# twip-sb2.net
KiCad netlist of a schematic drawn in EAGLE
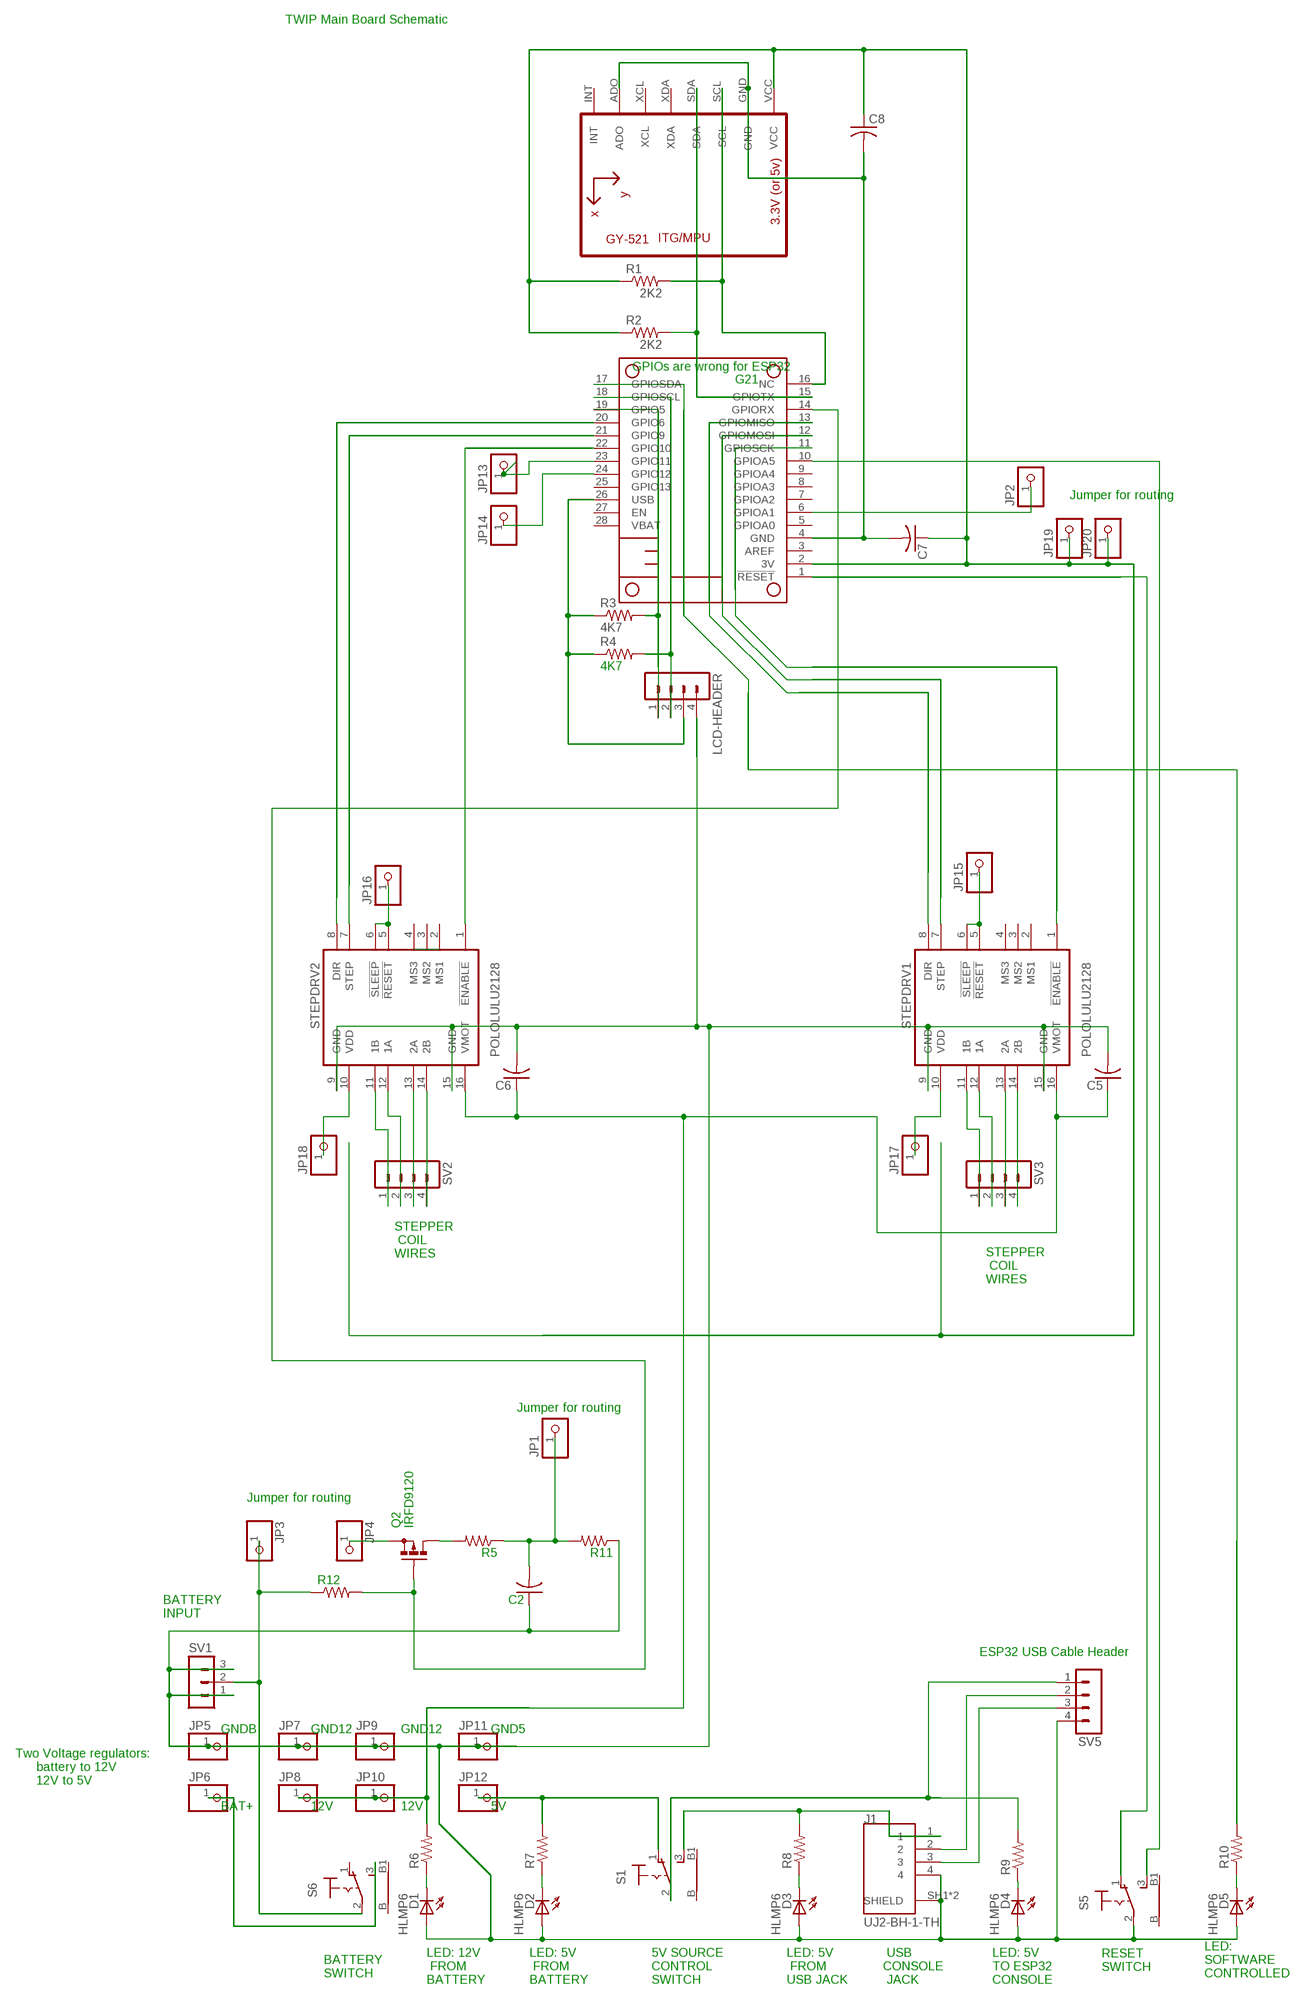
[diagram p0: schematic, sheet 1]

(export (version "E")
  (design (tool "Eeschema 10.0.6"))
  (components
    (comp (ref "C2")
      (value "C-US050-025X075")
      (footprint "eagle-import:C050-025X075")
      (libsource (lib "eagle-import") (part "C-US050-025X075"))
    )
    (comp (ref "C5")
      (value "C-US050-024X044")
      (footprint "eagle-import:C050-024X044")
      (libsource (lib "eagle-import") (part "C-US050-024X044"))
    )
    (comp (ref "C6")
      (value "C-US050-024X044")
      (footprint "eagle-import:C050-024X044")
      (libsource (lib "eagle-import") (part "C-US050-024X044"))
    )
    (comp (ref "C7")
      (value "C-US050-024X044")
      (footprint "eagle-import:C050-024X044")
      (libsource (lib "eagle-import") (part "C-US050-024X044"))
    )
    (comp (ref "C8")
      (value "C-US050-024X044")
      (footprint "eagle-import:C050-024X044")
      (libsource (lib "eagle-import") (part "C-US050-024X044"))
    )
    (comp (ref "D1")
      (value "HLMP6")
      (footprint "eagle-import:HLMP6")
      (fields (field (name "MF") "AGILENT TECHNOLOGIES") (field (name "MPN") "HLMP-6500"))
      (libsource (lib "eagle-import") (part "HLMP6"))
    )
    (comp (ref "D2")
      (value "HLMP6")
      (footprint "eagle-import:HLMP6")
      (fields (field (name "MF") "AGILENT TECHNOLOGIES") (field (name "MPN") "HLMP-6500"))
      (libsource (lib "eagle-import") (part "HLMP6"))
    )
    (comp (ref "D3")
      (value "HLMP6")
      (footprint "eagle-import:HLMP6")
      (fields (field (name "MF") "AGILENT TECHNOLOGIES") (field (name "MPN") "HLMP-6500"))
      (libsource (lib "eagle-import") (part "HLMP6"))
    )
    (comp (ref "D4")
      (value "HLMP6")
      (footprint "eagle-import:HLMP6")
      (fields (field (name "MF") "AGILENT TECHNOLOGIES") (field (name "MPN") "HLMP-6500"))
      (libsource (lib "eagle-import") (part "HLMP6"))
    )
    (comp (ref "D5")
      (value "HLMP6")
      (footprint "eagle-import:HLMP6")
      (fields (field (name "MF") "AGILENT TECHNOLOGIES") (field (name "MPN") "HLMP-6500"))
      (libsource (lib "eagle-import") (part "HLMP6"))
    )
    (comp (ref "J1")
      (value "UJ2-BH-1-TH")
      (footprint "eagle-import:CUI_UJ2-BH-1-TH")
      (fields (field (name "MANUFACTURER") "CUI INC"))
      (libsource (lib "eagle-import") (part "UJ2-BH-1-TH"))
    )
    (comp (ref "JP1")
      (value "PINHD-1X1")
      (footprint "eagle-import:1X01")
      (libsource (lib "eagle-import") (part "PINHD-1X1"))
    )
    (comp (ref "JP2")
      (value "PINHD-1X1")
      (footprint "eagle-import:1X01")
      (libsource (lib "eagle-import") (part "PINHD-1X1"))
    )
    (comp (ref "JP3")
      (value "PINHD-1X1")
      (footprint "eagle-import:1X01")
      (libsource (lib "eagle-import") (part "PINHD-1X1"))
    )
    (comp (ref "JP4")
      (value "PINHD-1X1")
      (footprint "eagle-import:1X01")
      (libsource (lib "eagle-import") (part "PINHD-1X1"))
    )
    (comp (ref "JP5")
      (value "PINHD-1X1")
      (footprint "eagle-import:1X01")
      (libsource (lib "eagle-import") (part "PINHD-1X1"))
    )
    (comp (ref "JP6")
      (value "PINHD-1X1")
      (footprint "eagle-import:1X01")
      (libsource (lib "eagle-import") (part "PINHD-1X1"))
    )
    (comp (ref "JP7")
      (value "PINHD-1X1")
      (footprint "eagle-import:1X01")
      (libsource (lib "eagle-import") (part "PINHD-1X1"))
    )
    (comp (ref "JP8")
      (value "PINHD-1X1")
      (footprint "eagle-import:1X01")
      (libsource (lib "eagle-import") (part "PINHD-1X1"))
    )
    (comp (ref "JP9")
      (value "PINHD-1X1")
      (footprint "eagle-import:1X01")
      (libsource (lib "eagle-import") (part "PINHD-1X1"))
    )
    (comp (ref "JP10")
      (value "PINHD-1X1")
      (footprint "eagle-import:1X01")
      (libsource (lib "eagle-import") (part "PINHD-1X1"))
    )
    (comp (ref "JP11")
      (value "PINHD-1X1")
      (footprint "eagle-import:1X01")
      (libsource (lib "eagle-import") (part "PINHD-1X1"))
    )
    (comp (ref "JP12")
      (value "PINHD-1X1")
      (footprint "eagle-import:1X01")
      (libsource (lib "eagle-import") (part "PINHD-1X1"))
    )
    (comp (ref "JP13")
      (value "PINHD-1X1")
      (footprint "eagle-import:1X01")
      (libsource (lib "eagle-import") (part "PINHD-1X1"))
    )
    (comp (ref "JP14")
      (value "PINHD-1X1")
      (footprint "eagle-import:1X01")
      (libsource (lib "eagle-import") (part "PINHD-1X1"))
    )
    (comp (ref "JP15")
      (value "PINHD-1X1")
      (footprint "eagle-import:1X01")
      (libsource (lib "eagle-import") (part "PINHD-1X1"))
    )
    (comp (ref "JP16")
      (value "PINHD-1X1")
      (footprint "eagle-import:1X01")
      (libsource (lib "eagle-import") (part "PINHD-1X1"))
    )
    (comp (ref "JP17")
      (value "PINHD-1X1")
      (footprint "eagle-import:1X01")
      (libsource (lib "eagle-import") (part "PINHD-1X1"))
    )
    (comp (ref "JP18")
      (value "PINHD-1X1")
      (footprint "eagle-import:1X01")
      (libsource (lib "eagle-import") (part "PINHD-1X1"))
    )
    (comp (ref "JP19")
      (value "PINHD-1X1")
      (footprint "eagle-import:1X01")
      (libsource (lib "eagle-import") (part "PINHD-1X1"))
    )
    (comp (ref "JP20")
      (value "PINHD-1X1")
      (footprint "eagle-import:1X01")
      (libsource (lib "eagle-import") (part "PINHD-1X1"))
    )
    (comp (ref "LCD-HEADER")
      (value "MA04-1")
      (footprint "eagle-import:MA04-1")
      (libsource (lib "eagle-import") (part "MA04-1"))
    )
    (comp (ref "MS2")
      (value "FEATHERWING_NOHOLES")
      (footprint "eagle-import:FEATHERWING_NOHOLES")
      (libsource (lib "eagle-import") (part "FEATHERWING_NOHOLES"))
    )
    (comp (ref "Q2")
      (value "IRFD9120")
      (footprint "eagle-import:C370-01")
      (libsource (lib "eagle-import") (part "IRFD9120"))
    )
    (comp (ref "R1")
      (value "2K2")
      (footprint "eagle-import:0309_12")
      (libsource (lib "eagle-import") (part "resistor_348_R-US_0309/12"))
    )
    (comp (ref "R2")
      (value "2K2")
      (footprint "eagle-import:0309_12")
      (libsource (lib "eagle-import") (part "resistor_348_R-US_0309/12"))
    )
    (comp (ref "R3")
      (value "4K7")
      (footprint "eagle-import:0309_12")
      (libsource (lib "eagle-import") (part "resistor_348_R-US_0309/12"))
    )
    (comp (ref "R4")
      (value "4K7")
      (footprint "eagle-import:0309_12")
      (libsource (lib "eagle-import") (part "resistor_348_R-US_0309/12"))
    )
    (comp (ref "R5")
      (value "R-US_0207/10")
      (footprint "eagle-import:0207_10")
      (libsource (lib "eagle-import") (part "R-US_0207/10"))
    )
    (comp (ref "R6")
      (value "R-US_0207/10")
      (footprint "eagle-import:0207_10")
      (libsource (lib "eagle-import") (part "R-US_0207/10"))
    )
    (comp (ref "R7")
      (value "R-US_0207/10")
      (footprint "eagle-import:0207_10")
      (libsource (lib "eagle-import") (part "R-US_0207/10"))
    )
    (comp (ref "R8")
      (value "R-US_0207/10")
      (footprint "eagle-import:0207_10")
      (libsource (lib "eagle-import") (part "R-US_0207/10"))
    )
    (comp (ref "R9")
      (value "R-US_0207/10")
      (footprint "eagle-import:0207_10")
      (libsource (lib "eagle-import") (part "R-US_0207/10"))
    )
    (comp (ref "R10")
      (value "R-US_0207/10")
      (footprint "eagle-import:0207_10")
      (libsource (lib "eagle-import") (part "R-US_0207/10"))
    )
    (comp (ref "R11")
      (value "R-US_0207/10")
      (footprint "eagle-import:0207_10")
      (libsource (lib "eagle-import") (part "R-US_0207/10"))
    )
    (comp (ref "R12")
      (value "R-US_0207/10")
      (footprint "eagle-import:0207_10")
      (libsource (lib "eagle-import") (part "R-US_0207/10"))
    )
    (comp (ref "S1")
      (value "9070-1W")
      (footprint "eagle-import:9070-1W")
      (libsource (lib "eagle-import") (part "9070-1W"))
    )
    (comp (ref "S5")
      (value "9070-1W")
      (footprint "eagle-import:9070-1W")
      (libsource (lib "eagle-import") (part "9070-1W"))
    )
    (comp (ref "S6")
      (value "9070-1W")
      (footprint "eagle-import:9070-1W")
      (libsource (lib "eagle-import") (part "9070-1W"))
    )
    (comp (ref "STEPDRV1")
      (value "POLOLULU2128")
      (footprint "eagle-import:POLOLULU2128")
      (libsource (lib "eagle-import") (part "POLOLULU2128"))
    )
    (comp (ref "STEPDRV2")
      (value "POLOLULU2128")
      (footprint "eagle-import:POLOLULU2128")
      (libsource (lib "eagle-import") (part "POLOLULU2128"))
    )
    (comp (ref "SV1")
      (value "MA03-1")
      (footprint "eagle-import:MA03-1")
      (libsource (lib "eagle-import") (part "MA03-1"))
    )
    (comp (ref "SV2")
      (value "MA04-1")
      (footprint "eagle-import:MA04-1")
      (libsource (lib "eagle-import") (part "MA04-1"))
    )
    (comp (ref "SV3")
      (value "MA04-1")
      (footprint "eagle-import:MA04-1")
      (libsource (lib "eagle-import") (part "MA04-1"))
    )
    (comp (ref "SV5")
      (value "MA04-1")
      (footprint "eagle-import:MA04-1")
      (libsource (lib "eagle-import") (part "MA04-1"))
    )
    (comp (ref "U1")
      (value "GY-521MPU6050")
      (footprint "eagle-import:GY-521")
      (libsource (lib "eagle-import") (part "GY-521MPU6050"))
    )
  )
  (nets
    (net (code "1") (name "/VBAT") (class "Default")
      (node (ref "MS2") (pin "28") (pinfunction "VBAT_28") (pintype "power_in"))
    )
    (net (code "2") (name "Net-(C2-Pad2)") (class "Default")
      (node (ref "C2") (pin "2") (pinfunction "2_2") (pintype "passive"))
      (node (ref "JP1") (pin "1") (pinfunction "1_1") (pintype "passive"))
      (node (ref "R11") (pin "2") (pinfunction "2_2") (pintype "passive"))
      (node (ref "R5") (pin "1") (pinfunction "1_1") (pintype "passive"))
    )
    (net (code "3") (name "Net-(D1-PadK)") (class "Default")
      (node (ref "D1") (pin "K") (pinfunction "K_K") (pintype "passive"))
      (node (ref "R6") (pin "1") (pinfunction "1_1") (pintype "passive"))
    )
    (net (code "4") (name "Net-(D2-PadK)") (class "Default")
      (node (ref "D2") (pin "K") (pinfunction "K_K") (pintype "passive"))
      (node (ref "R7") (pin "1") (pinfunction "1_1") (pintype "passive"))
    )
    (net (code "5") (name "Net-(D3-PadK)") (class "Default")
      (node (ref "D3") (pin "K") (pinfunction "K_K") (pintype "passive"))
      (node (ref "R8") (pin "1") (pinfunction "1_1") (pintype "passive"))
    )
    (net (code "6") (name "Net-(D4-PadK)") (class "Default")
      (node (ref "D4") (pin "K") (pinfunction "K_K") (pintype "passive"))
      (node (ref "R9") (pin "1") (pinfunction "1_1") (pintype "passive"))
    )
    (net (code "7") (name "Net-(D5-PadK)") (class "Default")
      (node (ref "D5") (pin "K") (pinfunction "K_K") (pintype "passive"))
      (node (ref "R10") (pin "1") (pinfunction "1_1") (pintype "passive"))
    )
    (net (code "8") (name "Net-(J1-Pad2)") (class "Default")
      (node (ref "J1") (pin "2") (pinfunction "2_2") (pintype "passive"))
      (node (ref "SV5") (pin "2") (pinfunction "2_2") (pintype "passive"))
    )
    (net (code "9") (name "Net-(J1-Pad3)") (class "Default")
      (node (ref "J1") (pin "3") (pinfunction "3_3") (pintype "passive"))
      (node (ref "SV5") (pin "3") (pinfunction "3_3") (pintype "passive"))
    )
    (net (code "10") (name "Net-(JP4-Pad1)") (class "Default")
      (node (ref "JP4") (pin "1") (pinfunction "1_1") (pintype "passive"))
      (node (ref "Q2") (pin "S") (pinfunction "S_S") (pintype "passive"))
    )
    (net (code "11") (name "Net-(MS2-3V)") (class "Default")
      (node (ref "C7") (pin "1") (pinfunction "1_1") (pintype "passive"))
      (node (ref "C8") (pin "1") (pinfunction "1_1") (pintype "passive"))
      (node (ref "JP19") (pin "1") (pinfunction "1_1") (pintype "passive"))
      (node (ref "JP20") (pin "1") (pinfunction "1_1") (pintype "passive"))
      (node (ref "MS2") (pin "2") (pinfunction "3V_2") (pintype "power_in"))
      (node (ref "R1") (pin "1") (pinfunction "1_1") (pintype "passive"))
      (node (ref "R2") (pin "1") (pinfunction "1_1") (pintype "passive"))
      (node (ref "U1") (pin "VCC") (pinfunction "VCC_VCC") (pintype "bidirectional"))
    )
    (net (code "12") (name "Net-(MS2-GND)") (class "Default")
      (node (ref "C7") (pin "2") (pinfunction "2_2") (pintype "passive"))
      (node (ref "C8") (pin "2") (pinfunction "2_2") (pintype "passive"))
      (node (ref "MS2") (pin "4") (pinfunction "GND_4") (pintype "power_in"))
      (node (ref "U1") (pin "ADO") (pinfunction "ADO_ADO") (pintype "bidirectional"))
      (node (ref "U1") (pin "GND") (pinfunction "GND_GND") (pintype "bidirectional"))
    )
    (net (code "13") (name "Net-(MS2-GPIO5)") (class "Default")
      (node (ref "LCD-HEADER") (pin "1") (pinfunction "1_1") (pintype "passive"))
      (node (ref "MS2") (pin "19") (pinfunction "GPIO5_19") (pintype "bidirectional"))
      (node (ref "R3") (pin "2") (pinfunction "2_2") (pintype "passive"))
    )
    (net (code "14") (name "Net-(MS2-GPIO6)") (class "Default")
      (node (ref "MS2") (pin "20") (pinfunction "GPIO6_20") (pintype "bidirectional"))
      (node (ref "STEPDRV2") (pin "8") (pinfunction "DIR_8") (pintype "input"))
    )
    (net (code "15") (name "Net-(MS2-GPIO9)") (class "Default")
      (node (ref "MS2") (pin "21") (pinfunction "GPIO9_21") (pintype "bidirectional"))
      (node (ref "STEPDRV2") (pin "7") (pinfunction "STEP_7") (pintype "input"))
    )
    (net (code "16") (name "Net-(MS2-GPIO10)") (class "Default")
      (node (ref "MS2") (pin "22") (pinfunction "GPIO10_22") (pintype "bidirectional"))
      (node (ref "STEPDRV2") (pin "1") (pinfunction "~{ENABLE}_1") (pintype "input"))
    )
    (net (code "17") (name "Net-(MS2-GPIO11)") (class "Default")
      (node (ref "JP13") (pin "1") (pinfunction "1_1") (pintype "passive"))
      (node (ref "MS2") (pin "23") (pinfunction "GPIO11_23") (pintype "bidirectional"))
    )
    (net (code "18") (name "Net-(MS2-GPIO12)") (class "Default")
      (node (ref "JP14") (pin "1") (pinfunction "1_1") (pintype "passive"))
      (node (ref "MS2") (pin "24") (pinfunction "GPIO12_24") (pintype "bidirectional"))
    )
    (net (code "19") (name "Net-(MS2-GPIOA1)") (class "Default")
      (node (ref "JP2") (pin "1") (pinfunction "1_1") (pintype "passive"))
      (node (ref "MS2") (pin "6") (pinfunction "GPIOA1_6") (pintype "bidirectional"))
    )
    (net (code "20") (name "Net-(MS2-GPIOA5)") (class "Default")
      (node (ref "MS2") (pin "10") (pinfunction "GPIOA5_10") (pintype "bidirectional"))
      (node (ref "S5") (pin "3") (pinfunction "S_3") (pintype "passive"))
    )
    (net (code "21") (name "Net-(MS2-GPIOMISO)") (class "Default")
      (node (ref "MS2") (pin "13") (pinfunction "GPIOMISO_13") (pintype "bidirectional"))
      (node (ref "STEPDRV1") (pin "8") (pinfunction "DIR_8") (pintype "input"))
    )
    (net (code "22") (name "Net-(MS2-GPIOMOSI)") (class "Default")
      (node (ref "MS2") (pin "12") (pinfunction "GPIOMOSI_12") (pintype "bidirectional"))
      (node (ref "STEPDRV1") (pin "7") (pinfunction "STEP_7") (pintype "input"))
    )
    (net (code "23") (name "Net-(MS2-GPIORX)") (class "Default")
      (node (ref "MS2") (pin "14") (pinfunction "GPIORX_14") (pintype "bidirectional"))
      (node (ref "Q2") (pin "G") (pinfunction "G_G") (pintype "passive"))
      (node (ref "R12") (pin "2") (pinfunction "2_2") (pintype "passive"))
    )
    (net (code "24") (name "Net-(MS2-GPIOSCK)") (class "Default")
      (node (ref "MS2") (pin "11") (pinfunction "GPIOSCK_11") (pintype "bidirectional"))
      (node (ref "STEPDRV1") (pin "1") (pinfunction "~{ENABLE}_1") (pintype "input"))
    )
    (net (code "25") (name "Net-(MS2-GPIOSCL)") (class "Default")
      (node (ref "LCD-HEADER") (pin "2") (pinfunction "2_2") (pintype "passive"))
      (node (ref "MS2") (pin "18") (pinfunction "GPIOSCL_18") (pintype "bidirectional"))
      (node (ref "R4") (pin "2") (pinfunction "2_2") (pintype "passive"))
    )
    (net (code "26") (name "Net-(MS2-GPIOSDA)") (class "Default")
      (node (ref "MS2") (pin "17") (pinfunction "GPIOSDA_17") (pintype "bidirectional"))
      (node (ref "R10") (pin "2") (pinfunction "2_2") (pintype "passive"))
    )
    (net (code "27") (name "Net-(MS2-GPIOTX)") (class "Default")
      (node (ref "MS2") (pin "15") (pinfunction "GPIOTX_15") (pintype "bidirectional"))
      (node (ref "R2") (pin "2") (pinfunction "2_2") (pintype "passive"))
      (node (ref "U1") (pin "SDA") (pinfunction "SDA_SDA") (pintype "bidirectional"))
    )
    (net (code "28") (name "Net-(MS2-NC)") (class "Default")
      (node (ref "MS2") (pin "16") (pinfunction "NC_16") (pintype "passive"))
      (node (ref "R1") (pin "2") (pinfunction "2_2") (pintype "passive"))
      (node (ref "U1") (pin "SCL") (pinfunction "SCL_SCL") (pintype "bidirectional"))
    )
    (net (code "29") (name "Net-(MS2-USB)") (class "Default")
      (node (ref "LCD-HEADER") (pin "3") (pinfunction "3_3") (pintype "passive"))
      (node (ref "MS2") (pin "26") (pinfunction "USB_26") (pintype "power_in"))
      (node (ref "R3") (pin "1") (pinfunction "1_1") (pintype "passive"))
      (node (ref "R4") (pin "1") (pinfunction "1_1") (pintype "passive"))
    )
    (net (code "30") (name "Net-(MS2-~{RESET})") (class "Default")
      (node (ref "MS2") (pin "1") (pinfunction "~{RESET}_1") (pintype "input"))
      (node (ref "S5") (pin "1") (pinfunction "O_1") (pintype "passive"))
    )
    (net (code "31") (name "Net-(Q2-D-PadD1)") (class "Default")
      (node (ref "Q2") (pin "D") (pinfunction "D_D") (pintype "passive"))
      (node (ref "Q2") (pin "D1") (pinfunction "D_D1") (pintype "passive"))
      (node (ref "R5") (pin "2") (pinfunction "2_2") (pintype "passive"))
    )
    (net (code "32") (name "Net-(S1-O)") (class "Default")
      (node (ref "JP12") (pin "1") (pinfunction "1_1") (pintype "passive"))
      (node (ref "R7") (pin "2") (pinfunction "2_2") (pintype "passive"))
      (node (ref "S1") (pin "1") (pinfunction "O_1") (pintype "passive"))
    )
    (net (code "33") (name "Net-(S1-P)") (class "Default")
      (node (ref "R9") (pin "2") (pinfunction "2_2") (pintype "passive"))
      (node (ref "S1") (pin "2") (pinfunction "P_2") (pintype "passive"))
      (node (ref "SV5") (pin "1") (pinfunction "1_1") (pintype "passive"))
    )
    (net (code "34") (name "Net-(S1-S)") (class "Default")
      (node (ref "J1") (pin "1") (pinfunction "1_1") (pintype "passive"))
      (node (ref "R8") (pin "2") (pinfunction "2_2") (pintype "passive"))
      (node (ref "S1") (pin "3") (pinfunction "S_3") (pintype "passive"))
    )
    (net (code "35") (name "Net-(S5-P)") (class "Default")
      (node (ref "C2") (pin "1") (pinfunction "1_1") (pintype "passive"))
      (node (ref "C5") (pin "2") (pinfunction "2_2") (pintype "passive"))
      (node (ref "C6") (pin "2") (pinfunction "2_2") (pintype "passive"))
      (node (ref "D1") (pin "A") (pinfunction "A_A") (pintype "passive"))
      (node (ref "D2") (pin "A") (pinfunction "A_A") (pintype "passive"))
      (node (ref "D3") (pin "A") (pinfunction "A_A") (pintype "passive"))
      (node (ref "D4") (pin "A") (pinfunction "A_A") (pintype "passive"))
      (node (ref "D5") (pin "A") (pinfunction "A_A") (pintype "passive"))
      (node (ref "J1") (pin "4") (pinfunction "4_4") (pintype "passive"))
      (node (ref "J1") (pin "SH1") (pinfunction "SHIELD_SH1") (pintype "passive"))
      (node (ref "J1") (pin "SH2") (pinfunction "SHIELD_SH2") (pintype "passive"))
      (node (ref "JP11") (pin "1") (pinfunction "1_1") (pintype "passive"))
      (node (ref "JP5") (pin "1") (pinfunction "1_1") (pintype "passive"))
      (node (ref "JP7") (pin "1") (pinfunction "1_1") (pintype "passive"))
      (node (ref "JP9") (pin "1") (pinfunction "1_1") (pintype "passive"))
      (node (ref "LCD-HEADER") (pin "4") (pinfunction "4_4") (pintype "passive"))
      (node (ref "R11") (pin "1") (pinfunction "1_1") (pintype "passive"))
      (node (ref "S5") (pin "2") (pinfunction "P_2") (pintype "passive"))
      (node (ref "STEPDRV1") (pin "15") (pinfunction "GND_15") (pintype "power_in"))
      (node (ref "STEPDRV1") (pin "9") (pinfunction "GND_9") (pintype "power_in"))
      (node (ref "STEPDRV2") (pin "15") (pinfunction "GND_15") (pintype "power_in"))
      (node (ref "STEPDRV2") (pin "9") (pinfunction "GND_9") (pintype "power_in"))
      (node (ref "SV1") (pin "1") (pinfunction "1_1") (pintype "passive"))
      (node (ref "SV1") (pin "3") (pinfunction "3_3") (pintype "passive"))
      (node (ref "SV5") (pin "4") (pinfunction "4_4") (pintype "passive"))
    )
    (net (code "36") (name "Net-(S6-P)") (class "Default")
      (node (ref "JP3") (pin "1") (pinfunction "1_1") (pintype "passive"))
      (node (ref "R12") (pin "1") (pinfunction "1_1") (pintype "passive"))
      (node (ref "S6") (pin "2") (pinfunction "P_2") (pintype "passive"))
      (node (ref "SV1") (pin "2") (pinfunction "2_2") (pintype "passive"))
    )
    (net (code "37") (name "Net-(S6-S)") (class "Default")
      (node (ref "JP6") (pin "1") (pinfunction "1_1") (pintype "passive"))
      (node (ref "S6") (pin "3") (pinfunction "S_3") (pintype "passive"))
    )
    (net (code "38") (name "Net-(STEPDRV1-1A)") (class "Default")
      (node (ref "STEPDRV1") (pin "12") (pinfunction "1A_12") (pintype "output"))
      (node (ref "SV3") (pin "2") (pinfunction "2_2") (pintype "passive"))
    )
    (net (code "39") (name "Net-(STEPDRV1-1B)") (class "Default")
      (node (ref "STEPDRV1") (pin "11") (pinfunction "1B_11") (pintype "output"))
      (node (ref "SV3") (pin "1") (pinfunction "1_1") (pintype "passive"))
    )
    (net (code "40") (name "Net-(STEPDRV1-2A)") (class "Default")
      (node (ref "STEPDRV1") (pin "13") (pinfunction "2A_13") (pintype "output"))
      (node (ref "SV3") (pin "3") (pinfunction "3_3") (pintype "passive"))
    )
    (net (code "41") (name "Net-(STEPDRV1-2B)") (class "Default")
      (node (ref "STEPDRV1") (pin "14") (pinfunction "2B_14") (pintype "output"))
      (node (ref "SV3") (pin "4") (pinfunction "4_4") (pintype "passive"))
    )
    (net (code "42") (name "Net-(STEPDRV1-VDD)") (class "Default")
      (node (ref "JP17") (pin "1") (pinfunction "1_1") (pintype "passive"))
      (node (ref "STEPDRV1") (pin "10") (pinfunction "VDD_10") (pintype "power_in"))
    )
    (net (code "43") (name "Net-(STEPDRV1-VMOT)") (class "Default")
      (node (ref "C5") (pin "1") (pinfunction "1_1") (pintype "passive"))
      (node (ref "C6") (pin "1") (pinfunction "1_1") (pintype "passive"))
      (node (ref "JP10") (pin "1") (pinfunction "1_1") (pintype "passive"))
      (node (ref "JP8") (pin "1") (pinfunction "1_1") (pintype "passive"))
      (node (ref "R6") (pin "2") (pinfunction "2_2") (pintype "passive"))
      (node (ref "STEPDRV1") (pin "16") (pinfunction "VMOT_16") (pintype "power_in"))
      (node (ref "STEPDRV2") (pin "16") (pinfunction "VMOT_16") (pintype "power_in"))
    )
    (net (code "44") (name "Net-(STEPDRV1-~{RESET})") (class "Default")
      (node (ref "JP15") (pin "1") (pinfunction "1_1") (pintype "passive"))
      (node (ref "STEPDRV1") (pin "5") (pinfunction "~{RESET}_5") (pintype "input"))
      (node (ref "STEPDRV1") (pin "6") (pinfunction "~{SLEEP}_6") (pintype "input"))
    )
    (net (code "45") (name "Net-(STEPDRV2-1A)") (class "Default")
      (node (ref "STEPDRV2") (pin "12") (pinfunction "1A_12") (pintype "output"))
      (node (ref "SV2") (pin "2") (pinfunction "2_2") (pintype "passive"))
    )
    (net (code "46") (name "Net-(STEPDRV2-1B)") (class "Default")
      (node (ref "STEPDRV2") (pin "11") (pinfunction "1B_11") (pintype "output"))
      (node (ref "SV2") (pin "1") (pinfunction "1_1") (pintype "passive"))
    )
    (net (code "47") (name "Net-(STEPDRV2-2A)") (class "Default")
      (node (ref "STEPDRV2") (pin "13") (pinfunction "2A_13") (pintype "output"))
      (node (ref "SV2") (pin "3") (pinfunction "3_3") (pintype "passive"))
    )
    (net (code "48") (name "Net-(STEPDRV2-2B)") (class "Default")
      (node (ref "STEPDRV2") (pin "14") (pinfunction "2B_14") (pintype "output"))
      (node (ref "SV2") (pin "4") (pinfunction "4_4") (pintype "passive"))
    )
    (net (code "49") (name "Net-(STEPDRV2-VDD)") (class "Default")
      (node (ref "JP18") (pin "1") (pinfunction "1_1") (pintype "passive"))
      (node (ref "STEPDRV2") (pin "10") (pinfunction "VDD_10") (pintype "power_in"))
    )
    (net (code "50") (name "Net-(STEPDRV2-~{RESET})") (class "Default")
      (node (ref "JP16") (pin "1") (pinfunction "1_1") (pintype "passive"))
      (node (ref "STEPDRV2") (pin "5") (pinfunction "~{RESET}_5") (pintype "input"))
      (node (ref "STEPDRV2") (pin "6") (pinfunction "~{SLEEP}_6") (pintype "input"))
    )
    (net (code "51") (name "unconnected-(MS2-AREF-Pad3)") (class "Default")
      (node (ref "MS2") (pin "3") (pinfunction "AREF_3") (pintype "passive"))
    )
    (net (code "52") (name "unconnected-(MS2-EN-Pad27)") (class "Default")
      (node (ref "MS2") (pin "27") (pinfunction "EN_27") (pintype "passive"))
    )
    (net (code "53") (name "unconnected-(MS2-GPIO13-Pad25)") (class "Default")
      (node (ref "MS2") (pin "25") (pinfunction "GPIO13_25") (pintype "bidirectional"))
    )
    (net (code "54") (name "unconnected-(MS2-GPIOA0-Pad5)") (class "Default")
      (node (ref "MS2") (pin "5") (pinfunction "GPIOA0_5") (pintype "bidirectional"))
    )
    (net (code "55") (name "unconnected-(MS2-GPIOA2-Pad7)") (class "Default")
      (node (ref "MS2") (pin "7") (pinfunction "GPIOA2_7") (pintype "bidirectional"))
    )
    (net (code "56") (name "unconnected-(MS2-GPIOA3-Pad8)") (class "Default")
      (node (ref "MS2") (pin "8") (pinfunction "GPIOA3_8") (pintype "bidirectional"))
    )
    (net (code "57") (name "unconnected-(MS2-GPIOA4-Pad9)") (class "Default")
      (node (ref "MS2") (pin "9") (pinfunction "GPIOA4_9") (pintype "bidirectional"))
    )
    (net (code "58") (name "unconnected-(S1-PadB)") (class "Default")
      (node (ref "S1") (pin "B") (pinfunction "B_B") (pintype "passive"))
    )
    (net (code "59") (name "unconnected-(S1-PadB1)") (class "Default")
      (node (ref "S1") (pin "B1") (pinfunction "B1_B1") (pintype "passive"))
    )
    (net (code "60") (name "unconnected-(S5-PadB)") (class "Default")
      (node (ref "S5") (pin "B") (pinfunction "B_B") (pintype "passive"))
    )
    (net (code "61") (name "unconnected-(S5-PadB1)") (class "Default")
      (node (ref "S5") (pin "B1") (pinfunction "B1_B1") (pintype "passive"))
    )
    (net (code "62") (name "unconnected-(S6-O-Pad1)") (class "Default")
      (node (ref "S6") (pin "1") (pinfunction "O_1") (pintype "passive"))
    )
    (net (code "63") (name "unconnected-(S6-PadB)") (class "Default")
      (node (ref "S6") (pin "B") (pinfunction "B_B") (pintype "passive"))
    )
    (net (code "64") (name "unconnected-(S6-PadB1)") (class "Default")
      (node (ref "S6") (pin "B1") (pinfunction "B1_B1") (pintype "passive"))
    )
    (net (code "65") (name "unconnected-(STEPDRV1-MS1-Pad2)") (class "Default")
      (node (ref "STEPDRV1") (pin "2") (pinfunction "MS1_2") (pintype "input"))
    )
    (net (code "66") (name "unconnected-(STEPDRV1-MS2-Pad3)") (class "Default")
      (node (ref "STEPDRV1") (pin "3") (pinfunction "MS2_3") (pintype "input"))
    )
    (net (code "67") (name "unconnected-(STEPDRV1-MS3-Pad4)") (class "Default")
      (node (ref "STEPDRV1") (pin "4") (pinfunction "MS3_4") (pintype "input"))
    )
    (net (code "68") (name "unconnected-(STEPDRV2-MS1-Pad2)") (class "Default")
      (node (ref "STEPDRV2") (pin "2") (pinfunction "MS1_2") (pintype "input"))
    )
    (net (code "69") (name "unconnected-(STEPDRV2-MS2-Pad3)") (class "Default")
      (node (ref "STEPDRV2") (pin "3") (pinfunction "MS2_3") (pintype "input"))
    )
    (net (code "70") (name "unconnected-(STEPDRV2-MS3-Pad4)") (class "Default")
      (node (ref "STEPDRV2") (pin "4") (pinfunction "MS3_4") (pintype "input"))
    )
    (net (code "71") (name "unconnected-(U1-PadINT)") (class "Default")
      (node (ref "U1") (pin "INT") (pinfunction "INT_INT") (pintype "bidirectional"))
    )
    (net (code "72") (name "unconnected-(U1-PadXCL)") (class "Default")
      (node (ref "U1") (pin "XCL") (pinfunction "XCL_XCL") (pintype "bidirectional"))
    )
    (net (code "73") (name "unconnected-(U1-PadXDA)") (class "Default")
      (node (ref "U1") (pin "XDA") (pinfunction "XDA_XDA") (pintype "bidirectional"))
    )
  )
)
